# Reset.net
KiCad netlist of a schematic drawn in Altium Designer
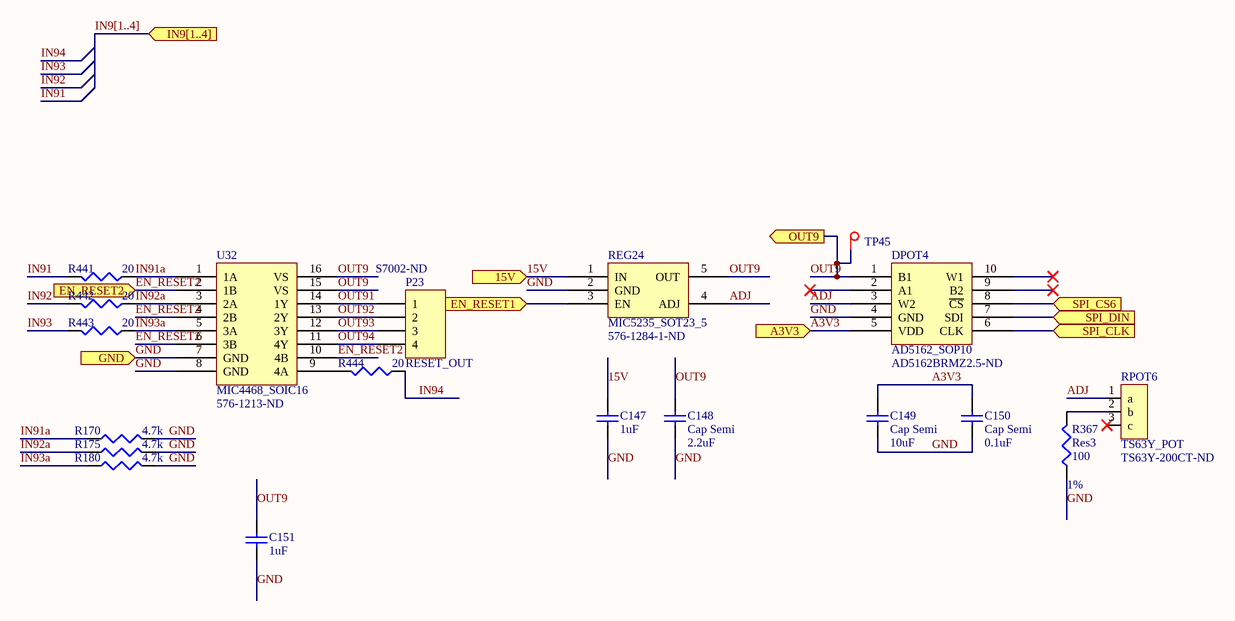
[diagram p0: Reset.SchDoc]

(export (version "E")
  (design (tool "Eeschema 10.0.6"))
  (components
    (comp (ref "C147")
      (value "1uF")
      (footprint "J1-0603")
      (description "Capacitor")
      (fields (field (name "Comment") "Cap") (field (name "PUBLISHER") "Altium Limited"))
      (libsource (lib "Miscellaneous Devices") (part "Cap"))
    )
    (comp (ref "C148")
      (value "Cap Semi")
      (footprint "J1-0603")
      (description "Capacitor (Semiconductor SIM Model)")
      (fields (field (name "ALTIUM_VALUE") "2.2uF") (field (name "PUBLISHER") "Altium Limited"))
      (libsource (lib "Miscellaneous Devices") (part "Cap Semi"))
    )
    (comp (ref "C149")
      (value "Cap Semi")
      (footprint "RES_0805")
      (description "Capacitor (Semiconductor SIM Model)")
      (fields (field (name "ALTIUM_VALUE") "10uF") (field (name "PUBLISHER") "Altium Limited"))
      (libsource (lib "Miscellaneous Devices") (part "Cap Semi"))
    )
    (comp (ref "C150")
      (value "Cap Semi")
      (footprint "J1-0603")
      (description "Capacitor (Semiconductor SIM Model)")
      (fields (field (name "ALTIUM_VALUE") "0.1uF") (field (name "PUBLISHER") "Altium Limited"))
      (libsource (lib "Miscellaneous Devices") (part "Cap Semi"))
    )
    (comp (ref "C151")
      (value "1uF")
      (footprint "J1-0603")
      (description "Capacitor")
      (fields (field (name "Comment") "Cap") (field (name "PUBLISHER") "Altium Limited"))
      (libsource (lib "Miscellaneous Devices") (part "Cap"))
    )
    (comp (ref "DPOT4")
      (value "AD5162_SOP10")
      (footprint "AD5162_SOP10")
      (fields (field (name "SUPPLIER PART NUMBER 1") "AD5162BRMZ2.5-ND"))
      (libsource (lib "Lib1") (part "AD5162_SOP10"))
    )
    (comp (ref "P23")
      (value "RESET_OUT")
      (footprint "HDR1X4")
      (description "Header, 4-Pin")
      (fields (field (name "SUPPLIER PART NUMBER 1") "S7002-ND") (field (name "PUBLISHER") "Altium Limited"))
      (libsource (lib "Miscellaneous Connectors") (part "Header 4"))
    )
    (comp (ref "R170")
      (value "4.7k")
      (footprint "J1-0603")
      (description "Resistor")
      (fields (field (name "Comment") "Res3") (field (name "PUBLISHER") "Altium Limited"))
      (libsource (lib "Miscellaneous Devices") (part "Res3"))
    )
    (comp (ref "R175")
      (value "4.7k")
      (footprint "J1-0603")
      (description "Resistor")
      (fields (field (name "Comment") "Res3") (field (name "PUBLISHER") "Altium Limited"))
      (libsource (lib "Miscellaneous Devices") (part "Res3"))
    )
    (comp (ref "R180")
      (value "4.7k")
      (footprint "J1-0603")
      (description "Resistor")
      (fields (field (name "Comment") "Res3") (field (name "PUBLISHER") "Altium Limited"))
      (libsource (lib "Miscellaneous Devices") (part "Res3"))
    )
    (comp (ref "R367")
      (value "Res3")
      (footprint "J1-0603")
      (description "Resistor")
      (fields
        (field (name "ALTIUM_VALUE") "100")
        (field (name "TOL") "1%")
        (field (name "PUBLISHER") "Altium Limited")
      )
      (libsource (lib "Miscellaneous Devices") (part "Res3"))
    )
    (comp (ref "R441")
      (value "20")
      (footprint "R0402")
      (description "Resistor")
      (fields (field (name "Comment") "Res3") (field (name "PUBLISHER") "Altium Limited"))
      (libsource (lib "Miscellaneous Devices") (part "Res3"))
    )
    (comp (ref "R442")
      (value "20")
      (footprint "R0402")
      (description "Resistor")
      (fields (field (name "Comment") "Res3") (field (name "PUBLISHER") "Altium Limited"))
      (libsource (lib "Miscellaneous Devices") (part "Res3"))
    )
    (comp (ref "R443")
      (value "20")
      (footprint "R0402")
      (description "Resistor")
      (fields (field (name "Comment") "Res3") (field (name "PUBLISHER") "Altium Limited"))
      (libsource (lib "Miscellaneous Devices") (part "Res3"))
    )
    (comp (ref "R444")
      (value "20")
      (footprint "R0402")
      (description "Resistor")
      (fields (field (name "Comment") "Res3") (field (name "PUBLISHER") "Altium Limited"))
      (libsource (lib "Miscellaneous Devices") (part "Res3"))
    )
    (comp (ref "REG24")
      (value "MIC5235_SOT23_5")
      (footprint "MIC5235_SOT23_5")
      (fields (field (name "SUPPLIER PART NUMBER 1") "576-1284-1-ND"))
      (libsource (lib "Lib1") (part "MIC5235_SOT23_5"))
    )
    (comp (ref "RPOT6")
      (value "TS63Y_POT")
      (footprint "TS63Y_POT")
      (fields (field (name "SUPPLIER PART NUMBER 1") "TS63Y-200CT-ND"))
      (libsource (lib "Lib1") (part "TS63Y_POT"))
    )
    (comp (ref "TP45")
      (value "Test Point")
      (footprint "TestPoint")
      (libsource (lib "Lib1") (part "Test Point"))
    )
    (comp (ref "U32")
      (value "MIC4468_SOIC16")
      (footprint "MIC4468_SOIC16")
      (fields (field (name "SUPPLIER PART NUMBER 1") "576-1213-ND"))
      (libsource (lib "Lib1") (part "MIC4468_SOIC16"))
    )
  )
  (nets
    (net (code "1") (name "/15V") (class "Default")
      (node (ref "C147") (pin "1") (pinfunction "1_1") (pintype "passive"))
      (node (ref "REG24") (pin "1") (pinfunction "IN_1") (pintype "passive"))
    )
    (net (code "2") (name "/A3V3") (class "Default")
      (node (ref "C149") (pin "2") (pinfunction "2_2") (pintype "passive"))
      (node (ref "C150") (pin "2") (pinfunction "2_2") (pintype "passive"))
      (node (ref "DPOT4") (pin "5") (pinfunction "VDD_5") (pintype "passive"))
    )
    (net (code "3") (name "/ADJ") (class "Default")
      (node (ref "DPOT4") (pin "3") (pinfunction "W2_3") (pintype "passive"))
      (node (ref "REG24") (pin "4") (pinfunction "ADJ_4") (pintype "passive"))
      (node (ref "RPOT6") (pin "1") (pinfunction "a_1") (pintype "passive"))
    )
    (net (code "4") (name "/EN_RESET1") (class "Default")
      (node (ref "REG24") (pin "3") (pinfunction "EN_3") (pintype "passive"))
    )
    (net (code "5") (name "/EN_RESET2") (class "Default")
      (node (ref "U32") (pin "10") (pinfunction "4B_10") (pintype "passive"))
      (node (ref "U32") (pin "2") (pinfunction "1B_2") (pintype "passive"))
      (node (ref "U32") (pin "4") (pinfunction "2B_4") (pintype "passive"))
      (node (ref "U32") (pin "6") (pinfunction "3B_6") (pintype "passive"))
    )
    (net (code "6") (name "/GND") (class "Default")
      (node (ref "C147") (pin "2") (pinfunction "2_2") (pintype "passive"))
      (node (ref "C148") (pin "1") (pinfunction "1_1") (pintype "passive"))
      (node (ref "C149") (pin "1") (pinfunction "1_1") (pintype "passive"))
      (node (ref "C150") (pin "1") (pinfunction "1_1") (pintype "passive"))
      (node (ref "C151") (pin "2") (pinfunction "2_2") (pintype "passive"))
      (node (ref "DPOT4") (pin "4") (pinfunction "GND_4") (pintype "passive"))
      (node (ref "R170") (pin "2") (pinfunction "2_2") (pintype "passive"))
      (node (ref "R175") (pin "2") (pinfunction "2_2") (pintype "passive"))
      (node (ref "R180") (pin "2") (pinfunction "2_2") (pintype "passive"))
      (node (ref "R367") (pin "1") (pinfunction "1_1") (pintype "passive"))
      (node (ref "REG24") (pin "2") (pinfunction "GND_2") (pintype "passive"))
      (node (ref "U32") (pin "7") (pinfunction "GND_7") (pintype "passive"))
      (node (ref "U32") (pin "8") (pinfunction "GND_8") (pintype "passive"))
    )
    (net (code "8") (name "/IN91") (class "Default")
      (node (ref "R441") (pin "2") (pinfunction "2_2") (pintype "passive"))
    )
    (net (code "9") (name "/IN91a") (class "Default")
      (node (ref "R170") (pin "1") (pinfunction "1_1") (pintype "passive"))
      (node (ref "R441") (pin "1") (pinfunction "1_1") (pintype "passive"))
      (node (ref "U32") (pin "1") (pinfunction "1A_1") (pintype "passive"))
    )
    (net (code "10") (name "/IN92") (class "Default")
      (node (ref "R442") (pin "2") (pinfunction "2_2") (pintype "passive"))
    )
    (net (code "11") (name "/IN92a") (class "Default")
      (node (ref "R175") (pin "1") (pinfunction "1_1") (pintype "passive"))
      (node (ref "R442") (pin "1") (pinfunction "1_1") (pintype "passive"))
      (node (ref "U32") (pin "3") (pinfunction "2A_3") (pintype "passive"))
    )
    (net (code "12") (name "/IN93") (class "Default")
      (node (ref "R443") (pin "2") (pinfunction "2_2") (pintype "passive"))
    )
    (net (code "13") (name "/IN93a") (class "Default")
      (node (ref "R180") (pin "1") (pinfunction "1_1") (pintype "passive"))
      (node (ref "R443") (pin "1") (pinfunction "1_1") (pintype "passive"))
      (node (ref "U32") (pin "5") (pinfunction "3A_5") (pintype "passive"))
    )
    (net (code "14") (name "/IN94") (class "Default")
      (node (ref "R444") (pin "1") (pinfunction "1_1") (pintype "passive"))
    )
    (net (code "15") (name "/OUT9") (class "Default")
      (node (ref "C148") (pin "2") (pinfunction "2_2") (pintype "passive"))
      (node (ref "C151") (pin "1") (pinfunction "1_1") (pintype "passive"))
      (node (ref "DPOT4") (pin "1") (pinfunction "B1_1") (pintype "passive"))
      (node (ref "REG24") (pin "5") (pinfunction "OUT_5") (pintype "passive"))
      (node (ref "TP45") (pin "1") (pinfunction "TP_1") (pintype "passive"))
      (node (ref "U32") (pin "15") (pinfunction "VS_15") (pintype "passive"))
      (node (ref "U32") (pin "16") (pinfunction "VS_16") (pintype "passive"))
    )
    (net (code "16") (name "/OUT91") (class "Default")
      (node (ref "P23") (pin "1") (pinfunction "1_1") (pintype "passive"))
      (node (ref "U32") (pin "14") (pinfunction "1Y_14") (pintype "passive"))
    )
    (net (code "17") (name "/OUT92") (class "Default")
      (node (ref "P23") (pin "2") (pinfunction "2_2") (pintype "passive"))
      (node (ref "U32") (pin "13") (pinfunction "2Y_13") (pintype "passive"))
    )
    (net (code "18") (name "/OUT93") (class "Default")
      (node (ref "P23") (pin "3") (pinfunction "3_3") (pintype "passive"))
      (node (ref "U32") (pin "12") (pinfunction "3Y_12") (pintype "passive"))
    )
    (net (code "19") (name "/OUT94") (class "Default")
      (node (ref "P23") (pin "4") (pinfunction "4_4") (pintype "passive"))
      (node (ref "U32") (pin "11") (pinfunction "4Y_11") (pintype "passive"))
    )
    (net (code "20") (name "/SPI_CLK") (class "Default")
      (node (ref "DPOT4") (pin "6") (pinfunction "CLK_6") (pintype "passive"))
    )
    (net (code "21") (name "/SPI_CS6") (class "Default")
      (node (ref "DPOT4") (pin "8") (pinfunction "~{CS}_8") (pintype "passive"))
    )
    (net (code "22") (name "/SPI_DIN") (class "Default")
      (node (ref "DPOT4") (pin "7") (pinfunction "SDI_7") (pintype "passive"))
    )
    (net (code "23") (name "Net-(RPOT6-b)") (class "Default")
      (node (ref "R367") (pin "2") (pinfunction "2_2") (pintype "passive"))
      (node (ref "RPOT6") (pin "2") (pinfunction "b_2") (pintype "passive"))
    )
    (net (code "24") (name "Net-(U32-4A)") (class "Default")
      (node (ref "R444") (pin "2") (pinfunction "2_2") (pintype "passive"))
      (node (ref "U32") (pin "9") (pinfunction "4A_9") (pintype "passive"))
    )
    (net (code "25") (name "unconnected-(DPOT4-A1-Pad2)") (class "Default")
      (node (ref "DPOT4") (pin "2") (pinfunction "A1_2") (pintype "passive+no_connect"))
    )
    (net (code "26") (name "unconnected-(DPOT4-B2-Pad9)") (class "Default")
      (node (ref "DPOT4") (pin "9") (pinfunction "B2_9") (pintype "passive+no_connect"))
    )
    (net (code "27") (name "unconnected-(DPOT4-W1-Pad10)") (class "Default")
      (node (ref "DPOT4") (pin "10") (pinfunction "W1_10") (pintype "passive+no_connect"))
    )
    (net (code "28") (name "unconnected-(RPOT6-c-Pad3)") (class "Default")
      (node (ref "RPOT6") (pin "3") (pinfunction "c_3") (pintype "passive+no_connect"))
    )
  )
)
